# CAN-SW.net
KiCad netlist of a schematic drawn in Altium Designer
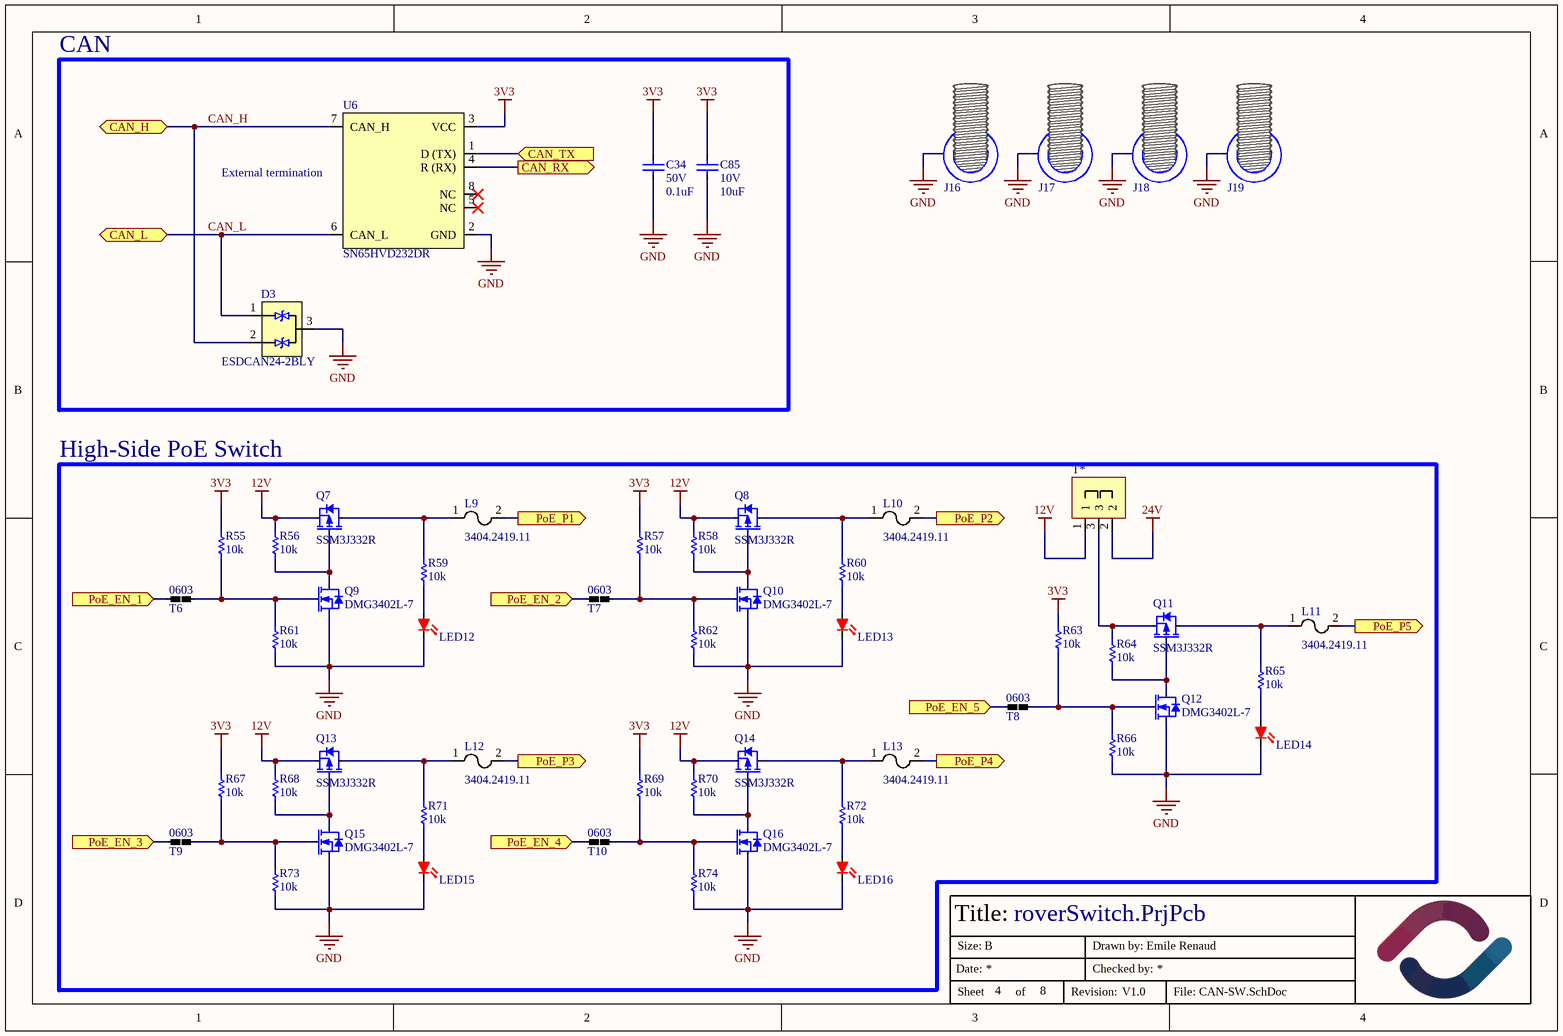
[diagram p0: CAN-SW.SchDoc]

(export (version "E")
  (design (tool "Eeschema 10.0.6"))
  (components
    (comp (ref "C34")
      (value "0.1uF")
      (footprint "CAPACITOR-0603")
      (description "Capacitor-0603-0.1uF-50V-X7R")
      (fields (field (name "VOLT") "50V"))
      (libsource (lib "Capacitors") (part "Capacitor-0603-0.1uF-50V-X7R"))
    )
    (comp (ref "C85")
      (value "10uF")
      (footprint "CAPACITOR-0603")
      (description "10 µF ±20% 10V Ceramic Capacitor X5R 0603 (1608 Metric)")
      (fields (field (name "VOLT") "10V") (field (name "Comment") "Capacitor-0603-10uF-10V-X5R"))
      (libsource (lib "Capacitors") (part "Capacitor-0603-10uF-10V-X5R"))
    )
    (comp (ref "D3")
      (value "ESDCAN24-2BLY")
      (footprint "SOT-23-3")
      (description "55V Clamp 6A (8/20µs) Ipp Tvs Diode Surface Mount SOT-23")
      (libsource (lib "diodes-tvs") (part "ESDCAN24-2BLY"))
    )
    (comp (ref "J16")
      (value "hole")
      (footprint "HOLE-3.40MM-M3-8MMEYELET")
      (description "Hole for M3 Bolt with 8mm pad")
      (libsource (lib "JumpersAndHoles") (part "Hole 3.40mm M3-Eyelet"))
    )
    (comp (ref "J17")
      (value "hole")
      (footprint "HOLE-3.40MM-M3-8MMEYELET")
      (description "Hole for M3 Bolt with 8mm pad")
      (libsource (lib "JumpersAndHoles") (part "Hole 3.40mm M3-Eyelet"))
    )
    (comp (ref "J18")
      (value "hole")
      (footprint "HOLE-3.40MM-M3-8MMEYELET")
      (description "Hole for M3 Bolt with 8mm pad")
      (libsource (lib "JumpersAndHoles") (part "Hole 3.40mm M3-Eyelet"))
    )
    (comp (ref "J19")
      (value "hole")
      (footprint "HOLE-3.40MM-M3-8MMEYELET")
      (description "Hole for M3 Bolt with 8mm pad")
      (libsource (lib "JumpersAndHoles") (part "Hole 3.40mm M3-Eyelet"))
    )
    (comp (ref "L9")
      (value "3404.2419.11")
      (footprint "2-SMD-Fuse")
      (libsource (lib "Fuses") (part "3404.2419.11"))
    )
    (comp (ref "L10")
      (value "3404.2419.11")
      (footprint "2-SMD-Fuse")
      (libsource (lib "Fuses") (part "3404.2419.11"))
    )
    (comp (ref "L11")
      (value "3404.2419.11")
      (footprint "2-SMD-Fuse")
      (libsource (lib "Fuses") (part "3404.2419.11"))
    )
    (comp (ref "L12")
      (value "3404.2419.11")
      (footprint "2-SMD-Fuse")
      (libsource (lib "Fuses") (part "3404.2419.11"))
    )
    (comp (ref "L13")
      (value "3404.2419.11")
      (footprint "2-SMD-Fuse")
      (libsource (lib "Fuses") (part "3404.2419.11"))
    )
    (comp (ref "LED12")
      (value "B1911USD-20D000114U1930")
      (footprint "LED-0603-2PIN")
      (description "LED RED CLEAR 0603 SMD")
      (libsource (lib "LEDs") (part "B1911USD-20D000114U1930"))
    )
    (comp (ref "LED13")
      (value "B1911USD-20D000114U1930")
      (footprint "LED-0603-2PIN")
      (description "LED RED CLEAR 0603 SMD")
      (libsource (lib "LEDs") (part "B1911USD-20D000114U1930"))
    )
    (comp (ref "LED14")
      (value "B1911USD-20D000114U1930")
      (footprint "LED-0603-2PIN")
      (description "LED RED CLEAR 0603 SMD")
      (libsource (lib "LEDs") (part "B1911USD-20D000114U1930"))
    )
    (comp (ref "LED15")
      (value "B1911USD-20D000114U1930")
      (footprint "LED-0603-2PIN")
      (description "LED RED CLEAR 0603 SMD")
      (libsource (lib "LEDs") (part "B1911USD-20D000114U1930"))
    )
    (comp (ref "LED16")
      (value "B1911USD-20D000114U1930")
      (footprint "LED-0603-2PIN")
      (description "LED RED CLEAR 0603 SMD")
      (libsource (lib "LEDs") (part "B1911USD-20D000114U1930"))
    )
    (comp (ref "Q7")
      (value "SSM3J332R")
      (footprint "SOT-23-3")
      (description "P-Channel 30 V 6A (Ta) 1W (Ta) Surface Mount SOT-23F")
      (libsource (lib "FET-P-Small") (part "SSM3J332R"))
    )
    (comp (ref "Q8")
      (value "SSM3J332R")
      (footprint "SOT-23-3")
      (description "P-Channel 30 V 6A (Ta) 1W (Ta) Surface Mount SOT-23F")
      (libsource (lib "FET-P-Small") (part "SSM3J332R"))
    )
    (comp (ref "Q9")
      (value "DMG3402L-7")
      (footprint "SOT-23-3")
      (description "N-Channel 30 V 4A (Ta) 1.4W (Ta) Surface Mount SOT-23-3")
      (libsource (lib "FET-N-Small") (part "DMG3402L-7"))
    )
    (comp (ref "Q10")
      (value "DMG3402L-7")
      (footprint "SOT-23-3")
      (description "N-Channel 30 V 4A (Ta) 1.4W (Ta) Surface Mount SOT-23-3")
      (libsource (lib "FET-N-Small") (part "DMG3402L-7"))
    )
    (comp (ref "Q11")
      (value "SSM3J332R")
      (footprint "SOT-23-3")
      (description "P-Channel 30 V 6A (Ta) 1W (Ta) Surface Mount SOT-23F")
      (libsource (lib "FET-P-Small") (part "SSM3J332R"))
    )
    (comp (ref "Q12")
      (value "DMG3402L-7")
      (footprint "SOT-23-3")
      (description "N-Channel 30 V 4A (Ta) 1.4W (Ta) Surface Mount SOT-23-3")
      (libsource (lib "FET-N-Small") (part "DMG3402L-7"))
    )
    (comp (ref "Q13")
      (value "SSM3J332R")
      (footprint "SOT-23-3")
      (description "P-Channel 30 V 6A (Ta) 1W (Ta) Surface Mount SOT-23F")
      (libsource (lib "FET-P-Small") (part "SSM3J332R"))
    )
    (comp (ref "Q14")
      (value "SSM3J332R")
      (footprint "SOT-23-3")
      (description "P-Channel 30 V 6A (Ta) 1W (Ta) Surface Mount SOT-23F")
      (libsource (lib "FET-P-Small") (part "SSM3J332R"))
    )
    (comp (ref "Q15")
      (value "DMG3402L-7")
      (footprint "SOT-23-3")
      (description "N-Channel 30 V 4A (Ta) 1.4W (Ta) Surface Mount SOT-23-3")
      (libsource (lib "FET-N-Small") (part "DMG3402L-7"))
    )
    (comp (ref "Q16")
      (value "DMG3402L-7")
      (footprint "SOT-23-3")
      (description "N-Channel 30 V 4A (Ta) 1.4W (Ta) Surface Mount SOT-23-3")
      (libsource (lib "FET-N-Small") (part "DMG3402L-7"))
    )
    (comp (ref "R55")
      (value "10k")
      (footprint "Resistor-0603")
      (description "Resistor0603-10k")
      (fields (field (name "Comment") "SMT resistor"))
      (libsource (lib "Resistors") (part "Resistor-0603-10k"))
    )
    (comp (ref "R56")
      (value "10k")
      (footprint "Resistor-0603")
      (description "Resistor0603-10k")
      (fields (field (name "Comment") "SMT resistor"))
      (libsource (lib "Resistors") (part "Resistor-0603-10k"))
    )
    (comp (ref "R57")
      (value "10k")
      (footprint "Resistor-0603")
      (description "Resistor0603-10k")
      (fields (field (name "Comment") "SMT resistor"))
      (libsource (lib "Resistors") (part "Resistor-0603-10k"))
    )
    (comp (ref "R58")
      (value "10k")
      (footprint "Resistor-0603")
      (description "Resistor0603-10k")
      (fields (field (name "Comment") "SMT resistor"))
      (libsource (lib "Resistors") (part "Resistor-0603-10k"))
    )
    (comp (ref "R59")
      (value "10k")
      (footprint "Resistor-0603")
      (description "Resistor0603-10k")
      (fields (field (name "Comment") "SMT resistor"))
      (libsource (lib "Resistors") (part "Resistor-0603-10k"))
    )
    (comp (ref "R60")
      (value "10k")
      (footprint "Resistor-0603")
      (description "Resistor0603-10k")
      (fields (field (name "Comment") "SMT resistor"))
      (libsource (lib "Resistors") (part "Resistor-0603-10k"))
    )
    (comp (ref "R61")
      (value "10k")
      (footprint "Resistor-0603")
      (description "Resistor0603-10k")
      (fields (field (name "Comment") "SMT resistor"))
      (libsource (lib "Resistors") (part "Resistor-0603-10k"))
    )
    (comp (ref "R62")
      (value "10k")
      (footprint "Resistor-0603")
      (description "Resistor0603-10k")
      (fields (field (name "Comment") "SMT resistor"))
      (libsource (lib "Resistors") (part "Resistor-0603-10k"))
    )
    (comp (ref "R63")
      (value "10k")
      (footprint "Resistor-0603")
      (description "Resistor0603-10k")
      (fields (field (name "Comment") "SMT resistor"))
      (libsource (lib "Resistors") (part "Resistor-0603-10k"))
    )
    (comp (ref "R64")
      (value "10k")
      (footprint "Resistor-0603")
      (description "Resistor0603-10k")
      (fields (field (name "Comment") "SMT resistor"))
      (libsource (lib "Resistors") (part "Resistor-0603-10k"))
    )
    (comp (ref "R65")
      (value "10k")
      (footprint "Resistor-0603")
      (description "Resistor0603-10k")
      (fields (field (name "Comment") "SMT resistor"))
      (libsource (lib "Resistors") (part "Resistor-0603-10k"))
    )
    (comp (ref "R66")
      (value "10k")
      (footprint "Resistor-0603")
      (description "Resistor0603-10k")
      (fields (field (name "Comment") "SMT resistor"))
      (libsource (lib "Resistors") (part "Resistor-0603-10k"))
    )
    (comp (ref "R67")
      (value "10k")
      (footprint "Resistor-0603")
      (description "Resistor0603-10k")
      (fields (field (name "Comment") "SMT resistor"))
      (libsource (lib "Resistors") (part "Resistor-0603-10k"))
    )
    (comp (ref "R68")
      (value "10k")
      (footprint "Resistor-0603")
      (description "Resistor0603-10k")
      (fields (field (name "Comment") "SMT resistor"))
      (libsource (lib "Resistors") (part "Resistor-0603-10k"))
    )
    (comp (ref "R69")
      (value "10k")
      (footprint "Resistor-0603")
      (description "Resistor0603-10k")
      (fields (field (name "Comment") "SMT resistor"))
      (libsource (lib "Resistors") (part "Resistor-0603-10k"))
    )
    (comp (ref "R70")
      (value "10k")
      (footprint "Resistor-0603")
      (description "Resistor0603-10k")
      (fields (field (name "Comment") "SMT resistor"))
      (libsource (lib "Resistors") (part "Resistor-0603-10k"))
    )
    (comp (ref "R71")
      (value "10k")
      (footprint "Resistor-0603")
      (description "Resistor0603-10k")
      (fields (field (name "Comment") "SMT resistor"))
      (libsource (lib "Resistors") (part "Resistor-0603-10k"))
    )
    (comp (ref "R72")
      (value "10k")
      (footprint "Resistor-0603")
      (description "Resistor0603-10k")
      (fields (field (name "Comment") "SMT resistor"))
      (libsource (lib "Resistors") (part "Resistor-0603-10k"))
    )
    (comp (ref "R73")
      (value "10k")
      (footprint "Resistor-0603")
      (description "Resistor0603-10k")
      (fields (field (name "Comment") "SMT resistor"))
      (libsource (lib "Resistors") (part "Resistor-0603-10k"))
    )
    (comp (ref "R74")
      (value "10k")
      (footprint "Resistor-0603")
      (description "Resistor0603-10k")
      (fields (field (name "Comment") "SMT resistor"))
      (libsource (lib "Resistors") (part "Resistor-0603-10k"))
    )
    (comp (ref "T*")
      (value "Jumper-3pos-small")
      (footprint "Jumper-3pos-small")
      (libsource (lib "JumpersAndHoles") (part "Jumper-3pos-small"))
    )
    (comp (ref "T6")
      (value "NetTie_0603_Short")
      (footprint "NetTie-0603-short")
      (libsource (lib "JumpersAndHoles") (part "NetTie_0603_Short"))
    )
    (comp (ref "T7")
      (value "NetTie_0603_Short")
      (footprint "NetTie-0603-short")
      (libsource (lib "JumpersAndHoles") (part "NetTie_0603_Short"))
    )
    (comp (ref "T8")
      (value "NetTie_0603_Short")
      (footprint "NetTie-0603-short")
      (libsource (lib "JumpersAndHoles") (part "NetTie_0603_Short"))
    )
    (comp (ref "T9")
      (value "NetTie_0603_Short")
      (footprint "NetTie-0603-short")
      (libsource (lib "JumpersAndHoles") (part "NetTie_0603_Short"))
    )
    (comp (ref "T10")
      (value "NetTie_0603_Short")
      (footprint "NetTie-0603-short")
      (libsource (lib "JumpersAndHoles") (part "NetTie_0603_Short"))
    )
    (comp (ref "U6")
      (value "SN65HVD232DR")
      (footprint "SOIC-8")
      (description "1/1 Transceiver Half CANbus 8-SOIC")
      (libsource (lib "Transceiver") (part "SN65HVD232DR"))
    )
  )
  (nets
    (net (code "1") (name "/CAN_H") (class "Default")
      (node (ref "D3") (pin "2") (pinfunction "GND_2") (pintype "passive"))
      (node (ref "U6") (pin "7") (pinfunction "CAN_H_7") (pintype "passive"))
    )
    (net (code "2") (name "/CAN_L") (class "Default")
      (node (ref "D3") (pin "1") (pinfunction "L2_1") (pintype "passive"))
      (node (ref "U6") (pin "6") (pinfunction "CAN_L_6") (pintype "passive"))
    )
    (net (code "3") (name "/CAN_RX") (class "Default")
      (node (ref "U6") (pin "4") (pinfunction "R_(RX)_4") (pintype "passive"))
    )
    (net (code "4") (name "/CAN_TX") (class "Default")
      (node (ref "U6") (pin "1") (pinfunction "D_(TX)_1") (pintype "passive"))
    )
    (net (code "5") (name "/PoE_EN_1") (class "Default")
      (node (ref "T6") (pin "2") (pinfunction "2_2") (pintype "passive"))
    )
    (net (code "6") (name "/PoE_EN_2") (class "Default")
      (node (ref "T7") (pin "2") (pinfunction "2_2") (pintype "passive"))
    )
    (net (code "7") (name "/PoE_EN_3") (class "Default")
      (node (ref "T9") (pin "2") (pinfunction "2_2") (pintype "passive"))
    )
    (net (code "8") (name "/PoE_EN_4") (class "Default")
      (node (ref "T10") (pin "2") (pinfunction "2_2") (pintype "passive"))
    )
    (net (code "9") (name "/PoE_EN_5") (class "Default")
      (node (ref "T8") (pin "2") (pinfunction "2_2") (pintype "passive"))
    )
    (net (code "10") (name "/PoE_P1") (class "Default")
      (node (ref "L9") (pin "2") (pinfunction "2_2") (pintype "passive"))
    )
    (net (code "11") (name "/PoE_P2") (class "Default")
      (node (ref "L10") (pin "2") (pinfunction "2_2") (pintype "passive"))
    )
    (net (code "12") (name "/PoE_P3") (class "Default")
      (node (ref "L12") (pin "2") (pinfunction "2_2") (pintype "passive"))
    )
    (net (code "13") (name "/PoE_P4") (class "Default")
      (node (ref "L13") (pin "2") (pinfunction "2_2") (pintype "passive"))
    )
    (net (code "14") (name "/PoE_P5") (class "Default")
      (node (ref "L11") (pin "2") (pinfunction "2_2") (pintype "passive"))
    )
    (net (code "15") (name "3V3") (class "Default")
      (node (ref "C34") (pin "2") (pinfunction "2_2") (pintype "passive"))
      (node (ref "C85") (pin "2") (pinfunction "2_2") (pintype "passive"))
      (node (ref "R55") (pin "2") (pinfunction "2_2") (pintype "passive"))
      (node (ref "R57") (pin "2") (pinfunction "2_2") (pintype "passive"))
      (node (ref "R63") (pin "2") (pinfunction "2_2") (pintype "passive"))
      (node (ref "R67") (pin "2") (pinfunction "2_2") (pintype "passive"))
      (node (ref "R69") (pin "2") (pinfunction "2_2") (pintype "passive"))
      (node (ref "U6") (pin "3") (pinfunction "VCC_3") (pintype "passive"))
    )
    (net (code "16") (name "12V") (class "Default")
      (node (ref "Q13") (pin "2") (pinfunction "S_2") (pintype "passive"))
      (node (ref "Q14") (pin "2") (pinfunction "S_2") (pintype "passive"))
      (node (ref "Q7") (pin "2") (pinfunction "S_2") (pintype "passive"))
      (node (ref "Q8") (pin "2") (pinfunction "S_2") (pintype "passive"))
      (node (ref "R56") (pin "2") (pinfunction "2_2") (pintype "passive"))
      (node (ref "R58") (pin "2") (pinfunction "2_2") (pintype "passive"))
      (node (ref "R68") (pin "2") (pinfunction "2_2") (pintype "passive"))
      (node (ref "R70") (pin "2") (pinfunction "2_2") (pintype "passive"))
      (node (ref "T*") (pin "1") (pinfunction "1_1") (pintype "passive"))
    )
    (net (code "17") (name "24V") (class "Default")
      (node (ref "T*") (pin "2") (pinfunction "2_2") (pintype "passive"))
    )
    (net (code "18") (name "GND") (class "Default")
      (node (ref "C34") (pin "1") (pinfunction "1_1") (pintype "passive"))
      (node (ref "C85") (pin "1") (pinfunction "1_1") (pintype "passive"))
      (node (ref "D3") (pin "3") (pinfunction "L3_3") (pintype "passive"))
      (node (ref "J16") (pin "1") (pinfunction "1_1") (pintype "passive"))
      (node (ref "J17") (pin "1") (pinfunction "1_1") (pintype "passive"))
      (node (ref "J18") (pin "1") (pinfunction "1_1") (pintype "passive"))
      (node (ref "J19") (pin "1") (pinfunction "1_1") (pintype "passive"))
      (node (ref "LED12") (pin "1") (pinfunction "K_1") (pintype "passive"))
      (node (ref "LED13") (pin "1") (pinfunction "K_1") (pintype "passive"))
      (node (ref "LED14") (pin "1") (pinfunction "K_1") (pintype "passive"))
      (node (ref "LED15") (pin "1") (pinfunction "K_1") (pintype "passive"))
      (node (ref "LED16") (pin "1") (pinfunction "K_1") (pintype "passive"))
      (node (ref "Q10") (pin "2") (pinfunction "S_2") (pintype "passive"))
      (node (ref "Q12") (pin "2") (pinfunction "S_2") (pintype "passive"))
      (node (ref "Q15") (pin "2") (pinfunction "S_2") (pintype "passive"))
      (node (ref "Q16") (pin "2") (pinfunction "S_2") (pintype "passive"))
      (node (ref "Q9") (pin "2") (pinfunction "S_2") (pintype "passive"))
      (node (ref "R61") (pin "1") (pinfunction "1_1") (pintype "passive"))
      (node (ref "R62") (pin "1") (pinfunction "1_1") (pintype "passive"))
      (node (ref "R66") (pin "1") (pinfunction "1_1") (pintype "passive"))
      (node (ref "R73") (pin "1") (pinfunction "1_1") (pintype "passive"))
      (node (ref "R74") (pin "1") (pinfunction "1_1") (pintype "passive"))
      (node (ref "U6") (pin "2") (pinfunction "GND_2") (pintype "passive"))
    )
    (net (code "19") (name "Net-(LED12-R)") (class "Default")
      (node (ref "LED12") (pin "2") (pinfunction "R_2") (pintype "passive"))
      (node (ref "R59") (pin "1") (pinfunction "1_1") (pintype "passive"))
    )
    (net (code "20") (name "Net-(LED13-R)") (class "Default")
      (node (ref "LED13") (pin "2") (pinfunction "R_2") (pintype "passive"))
      (node (ref "R60") (pin "1") (pinfunction "1_1") (pintype "passive"))
    )
    (net (code "21") (name "Net-(LED14-R)") (class "Default")
      (node (ref "LED14") (pin "2") (pinfunction "R_2") (pintype "passive"))
      (node (ref "R65") (pin "1") (pinfunction "1_1") (pintype "passive"))
    )
    (net (code "22") (name "Net-(LED15-R)") (class "Default")
      (node (ref "LED15") (pin "2") (pinfunction "R_2") (pintype "passive"))
      (node (ref "R71") (pin "1") (pinfunction "1_1") (pintype "passive"))
    )
    (net (code "23") (name "Net-(LED16-R)") (class "Default")
      (node (ref "LED16") (pin "2") (pinfunction "R_2") (pintype "passive"))
      (node (ref "R72") (pin "1") (pinfunction "1_1") (pintype "passive"))
    )
    (net (code "24") (name "Net-(Q7-D)") (class "Default")
      (node (ref "L9") (pin "1") (pinfunction "1_1") (pintype "passive"))
      (node (ref "Q7") (pin "3") (pinfunction "D_3") (pintype "passive"))
      (node (ref "R59") (pin "2") (pinfunction "2_2") (pintype "passive"))
    )
    (net (code "25") (name "Net-(Q7-G)") (class "Default")
      (node (ref "Q7") (pin "1") (pinfunction "G_1") (pintype "passive"))
      (node (ref "Q9") (pin "3") (pinfunction "D_3") (pintype "passive"))
      (node (ref "R56") (pin "1") (pinfunction "1_1") (pintype "passive"))
    )
    (net (code "26") (name "Net-(Q8-D)") (class "Default")
      (node (ref "L10") (pin "1") (pinfunction "1_1") (pintype "passive"))
      (node (ref "Q8") (pin "3") (pinfunction "D_3") (pintype "passive"))
      (node (ref "R60") (pin "2") (pinfunction "2_2") (pintype "passive"))
    )
    (net (code "27") (name "Net-(Q9-G)") (class "Default")
      (node (ref "Q9") (pin "1") (pinfunction "G_1") (pintype "passive"))
      (node (ref "R55") (pin "1") (pinfunction "1_1") (pintype "passive"))
      (node (ref "R61") (pin "2") (pinfunction "2_2") (pintype "passive"))
      (node (ref "T6") (pin "1") (pinfunction "1_1") (pintype "passive"))
    )
    (net (code "28") (name "Net-(Q10-D)") (class "Default")
      (node (ref "Q10") (pin "3") (pinfunction "D_3") (pintype "passive"))
      (node (ref "Q8") (pin "1") (pinfunction "G_1") (pintype "passive"))
      (node (ref "R58") (pin "1") (pinfunction "1_1") (pintype "passive"))
    )
    (net (code "29") (name "Net-(Q10-G)") (class "Default")
      (node (ref "Q10") (pin "1") (pinfunction "G_1") (pintype "passive"))
      (node (ref "R57") (pin "1") (pinfunction "1_1") (pintype "passive"))
      (node (ref "R62") (pin "2") (pinfunction "2_2") (pintype "passive"))
      (node (ref "T7") (pin "1") (pinfunction "1_1") (pintype "passive"))
    )
    (net (code "30") (name "Net-(Q11-D)") (class "Default")
      (node (ref "L11") (pin "1") (pinfunction "1_1") (pintype "passive"))
      (node (ref "Q11") (pin "3") (pinfunction "D_3") (pintype "passive"))
      (node (ref "R65") (pin "2") (pinfunction "2_2") (pintype "passive"))
    )
    (net (code "31") (name "Net-(Q11-G)") (class "Default")
      (node (ref "Q11") (pin "1") (pinfunction "G_1") (pintype "passive"))
      (node (ref "Q12") (pin "3") (pinfunction "D_3") (pintype "passive"))
      (node (ref "R64") (pin "1") (pinfunction "1_1") (pintype "passive"))
    )
    (net (code "32") (name "Net-(Q11-S)") (class "Default")
      (node (ref "Q11") (pin "2") (pinfunction "S_2") (pintype "passive"))
      (node (ref "R64") (pin "2") (pinfunction "2_2") (pintype "passive"))
      (node (ref "T*") (pin "3") (pinfunction "3_3") (pintype "passive"))
    )
    (net (code "33") (name "Net-(Q12-G)") (class "Default")
      (node (ref "Q12") (pin "1") (pinfunction "G_1") (pintype "passive"))
      (node (ref "R63") (pin "1") (pinfunction "1_1") (pintype "passive"))
      (node (ref "R66") (pin "2") (pinfunction "2_2") (pintype "passive"))
      (node (ref "T8") (pin "1") (pinfunction "1_1") (pintype "passive"))
    )
    (net (code "34") (name "Net-(Q13-D)") (class "Default")
      (node (ref "L12") (pin "1") (pinfunction "1_1") (pintype "passive"))
      (node (ref "Q13") (pin "3") (pinfunction "D_3") (pintype "passive"))
      (node (ref "R71") (pin "2") (pinfunction "2_2") (pintype "passive"))
    )
    (net (code "35") (name "Net-(Q13-G)") (class "Default")
      (node (ref "Q13") (pin "1") (pinfunction "G_1") (pintype "passive"))
      (node (ref "Q15") (pin "3") (pinfunction "D_3") (pintype "passive"))
      (node (ref "R68") (pin "1") (pinfunction "1_1") (pintype "passive"))
    )
    (net (code "36") (name "Net-(Q14-D)") (class "Default")
      (node (ref "L13") (pin "1") (pinfunction "1_1") (pintype "passive"))
      (node (ref "Q14") (pin "3") (pinfunction "D_3") (pintype "passive"))
      (node (ref "R72") (pin "2") (pinfunction "2_2") (pintype "passive"))
    )
    (net (code "37") (name "Net-(Q14-G)") (class "Default")
      (node (ref "Q14") (pin "1") (pinfunction "G_1") (pintype "passive"))
      (node (ref "Q16") (pin "3") (pinfunction "D_3") (pintype "passive"))
      (node (ref "R70") (pin "1") (pinfunction "1_1") (pintype "passive"))
    )
    (net (code "38") (name "Net-(Q15-G)") (class "Default")
      (node (ref "Q15") (pin "1") (pinfunction "G_1") (pintype "passive"))
      (node (ref "R67") (pin "1") (pinfunction "1_1") (pintype "passive"))
      (node (ref "R73") (pin "2") (pinfunction "2_2") (pintype "passive"))
      (node (ref "T9") (pin "1") (pinfunction "1_1") (pintype "passive"))
    )
    (net (code "39") (name "Net-(Q16-G)") (class "Default")
      (node (ref "Q16") (pin "1") (pinfunction "G_1") (pintype "passive"))
      (node (ref "R69") (pin "1") (pinfunction "1_1") (pintype "passive"))
      (node (ref "R74") (pin "2") (pinfunction "2_2") (pintype "passive"))
      (node (ref "T10") (pin "1") (pinfunction "1_1") (pintype "passive"))
    )
    (net (code "40") (name "unconnected-(U6-NC-Pad5)") (class "Default")
      (node (ref "U6") (pin "5") (pinfunction "NC_5") (pintype "passive+no_connect"))
    )
    (net (code "41") (name "unconnected-(U6-NC-Pad8)") (class "Default")
      (node (ref "U6") (pin "8") (pinfunction "NC_8") (pintype "passive+no_connect"))
    )
  )
)
